# Arduino_Uno.net
KiCad netlist of a schematic drawn in EAGLE
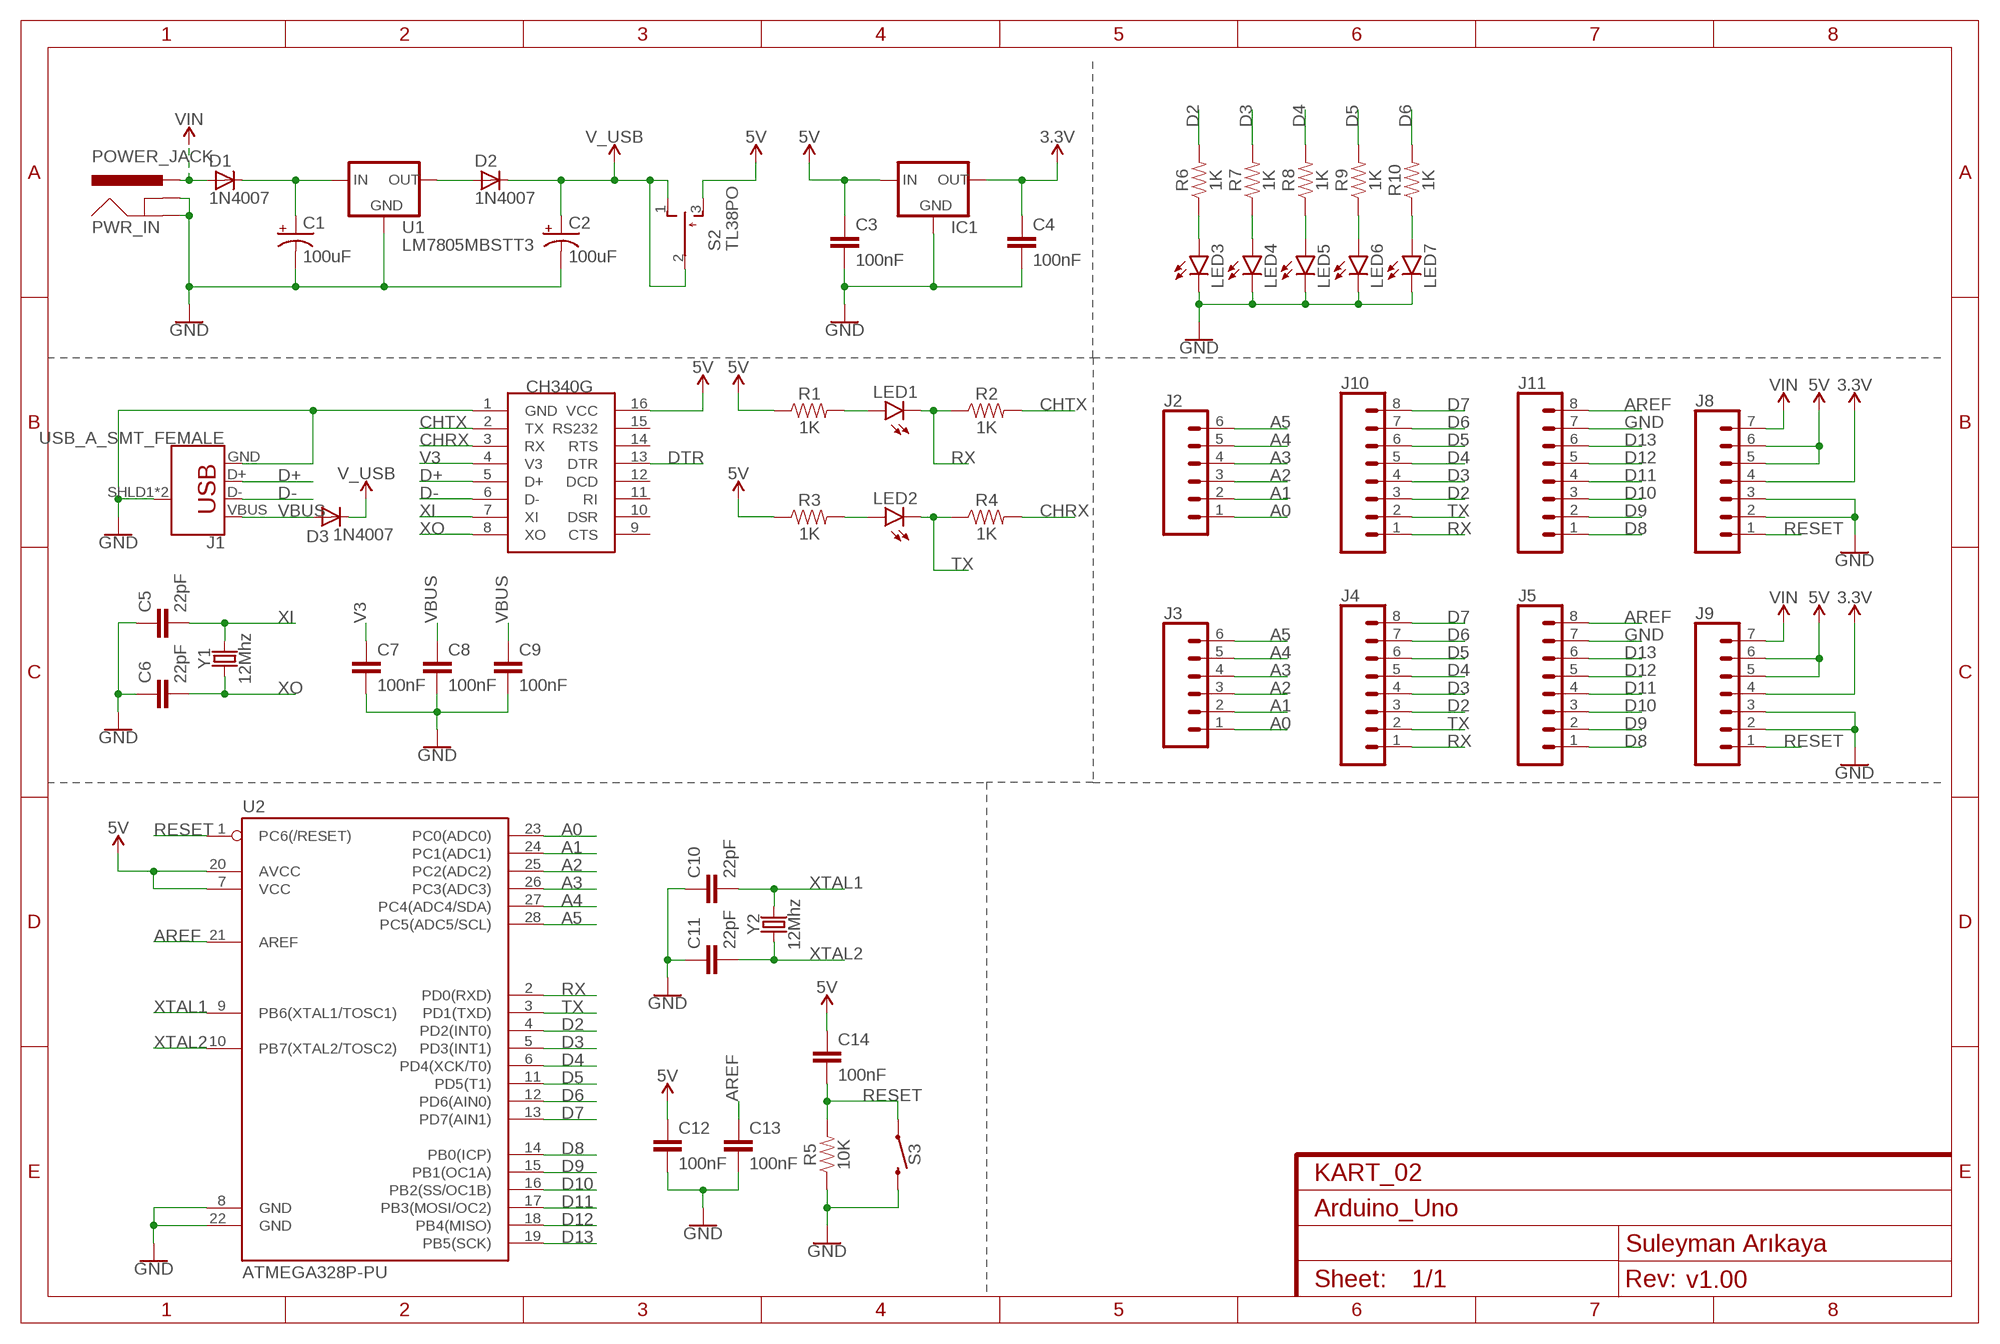
[diagram p0: schematic, sheet 1]

(export (version "E")
  (design (tool "Eeschema 10.0.6"))
  (components
    (comp (ref "C1")
      (value "100uF")
      (footprint "eagle-import:PANASONIC_D")
      (libsource (lib "eagle-import") (part "100UF-POLAR-25V-20%(ELEC)"))
    )
    (comp (ref "C2")
      (value "100uF")
      (footprint "eagle-import:PANASONIC_D")
      (libsource (lib "eagle-import") (part "100UF-POLAR-25V-20%(ELEC)"))
    )
    (comp (ref "C3")
      (value "100nF")
      (footprint "eagle-import:0805")
      (libsource (lib "eagle-import") (part "1.0UF-0805-25V-10%"))
    )
    (comp (ref "C4")
      (value "100nF")
      (footprint "eagle-import:0805")
      (libsource (lib "eagle-import") (part "1.0UF-0805-25V-10%"))
    )
    (comp (ref "C5")
      (value "22pF")
      (footprint "eagle-import:0805")
      (libsource (lib "eagle-import") (part "1.0UF-0805-25V-10%"))
    )
    (comp (ref "C6")
      (value "22pF")
      (footprint "eagle-import:0805")
      (libsource (lib "eagle-import") (part "1.0UF-0805-25V-10%"))
    )
    (comp (ref "C7")
      (value "100nF")
      (footprint "eagle-import:0805")
      (libsource (lib "eagle-import") (part "1.0UF-0805-25V-10%"))
    )
    (comp (ref "C8")
      (value "100nF")
      (footprint "eagle-import:0805")
      (libsource (lib "eagle-import") (part "1.0UF-0805-25V-10%"))
    )
    (comp (ref "C9")
      (value "100nF")
      (footprint "eagle-import:0805")
      (libsource (lib "eagle-import") (part "1.0UF-0805-25V-10%"))
    )
    (comp (ref "C10")
      (value "22pF")
      (footprint "eagle-import:0805")
      (libsource (lib "eagle-import") (part "1.0UF-0805-25V-10%"))
    )
    (comp (ref "C11")
      (value "22pF")
      (footprint "eagle-import:0805")
      (libsource (lib "eagle-import") (part "1.0UF-0805-25V-10%"))
    )
    (comp (ref "C12")
      (value "100nF")
      (footprint "eagle-import:0805")
      (libsource (lib "eagle-import") (part "1.0UF-0805-25V-10%"))
    )
    (comp (ref "C13")
      (value "100nF")
      (footprint "eagle-import:0805")
      (libsource (lib "eagle-import") (part "1.0UF-0805-25V-10%"))
    )
    (comp (ref "C14")
      (value "100nF")
      (footprint "eagle-import:0805")
      (libsource (lib "eagle-import") (part "1.0UF-0805-25V-10%"))
    )
    (comp (ref "D1")
      (value "1N4007")
      (footprint "eagle-import:SMA")
      (libsource (lib "eagle-import") (part "1N4007"))
    )
    (comp (ref "D2")
      (value "1N4007")
      (footprint "eagle-import:SMA")
      (libsource (lib "eagle-import") (part "1N4007"))
    )
    (comp (ref "D3")
      (value "1N4007")
      (footprint "eagle-import:SMA")
      (libsource (lib "eagle-import") (part "1N4007"))
    )
    (comp (ref "IC1")
      (value "LM1117")
      (footprint "eagle-import:SOT223")
      (libsource (lib "eagle-import") (part "LM1117"))
    )
    (comp (ref "J1")
      (value "USB_A_SMT_FEMALE")
      (footprint "eagle-import:USB-A-S-SILK-FEMALE")
      (libsource (lib "eagle-import") (part "USB_A_SMT_FEMALE"))
    )
    (comp (ref "J2")
      (value "CONN_06NO_SILK_FEMALE_PTH")
      (footprint "eagle-import:1X06_NO_SILK")
      (libsource (lib "eagle-import") (part "CONN_06NO_SILK_FEMALE_PTH"))
    )
    (comp (ref "J3")
      (value "CONN_06NO_SILK_FEMALE_PTH")
      (footprint "eagle-import:1X06_NO_SILK")
      (libsource (lib "eagle-import") (part "CONN_06NO_SILK_FEMALE_PTH"))
    )
    (comp (ref "J4")
      (value "CONN_08\"")
      (footprint "eagle-import:1X08")
      (libsource (lib "eagle-import") (part "CONN_08{dblquote}"))
    )
    (comp (ref "J5")
      (value "CONN_08\"")
      (footprint "eagle-import:1X08")
      (libsource (lib "eagle-import") (part "CONN_08{dblquote}"))
    )
    (comp (ref "J8")
      (value "CONN_07")
      (footprint "eagle-import:1X07")
      (libsource (lib "eagle-import") (part "CONN_07"))
    )
    (comp (ref "J9")
      (value "CONN_07")
      (footprint "eagle-import:1X07")
      (libsource (lib "eagle-import") (part "CONN_07"))
    )
    (comp (ref "J10")
      (value "CONN_08\"")
      (footprint "eagle-import:1X08")
      (libsource (lib "eagle-import") (part "CONN_08{dblquote}"))
    )
    (comp (ref "J11")
      (value "CONN_08\"")
      (footprint "eagle-import:1X08")
      (libsource (lib "eagle-import") (part "CONN_08{dblquote}"))
    )
    (comp (ref "LED1")
      (value "LEDSML0805")
      (footprint "eagle-import:SML0805")
      (libsource (lib "eagle-import") (part "LEDSML0805"))
    )
    (comp (ref "LED2")
      (value "LEDSML0805")
      (footprint "eagle-import:SML0805")
      (libsource (lib "eagle-import") (part "LEDSML0805"))
    )
    (comp (ref "LED3")
      (value "LEDSML0805")
      (footprint "eagle-import:SML0805")
      (libsource (lib "eagle-import") (part "LEDSML0805"))
    )
    (comp (ref "LED4")
      (value "LEDSML0805")
      (footprint "eagle-import:SML0805")
      (libsource (lib "eagle-import") (part "LEDSML0805"))
    )
    (comp (ref "LED5")
      (value "LEDSML0805")
      (footprint "eagle-import:SML0805")
      (libsource (lib "eagle-import") (part "LEDSML0805"))
    )
    (comp (ref "LED6")
      (value "LEDSML0805")
      (footprint "eagle-import:SML0805")
      (libsource (lib "eagle-import") (part "LEDSML0805"))
    )
    (comp (ref "LED7")
      (value "LEDSML0805")
      (footprint "eagle-import:SML0805")
      (libsource (lib "eagle-import") (part "LEDSML0805"))
    )
    (comp (ref "PWR_IN")
      (value "POWER_JACK")
      (footprint "eagle-import:POWER_JACK_PTH")
      (libsource (lib "eagle-import") (part "POWER_JACK"))
    )
    (comp (ref "R1")
      (value "1K")
      (footprint "eagle-import:0805")
      (libsource (lib "eagle-import") (part "RESISTOR0805"))
    )
    (comp (ref "R2")
      (value "1K")
      (footprint "eagle-import:0805")
      (libsource (lib "eagle-import") (part "RESISTOR0805"))
    )
    (comp (ref "R3")
      (value "1K")
      (footprint "eagle-import:0805")
      (libsource (lib "eagle-import") (part "RESISTOR0805"))
    )
    (comp (ref "R4")
      (value "1K")
      (footprint "eagle-import:0805")
      (libsource (lib "eagle-import") (part "RESISTOR0805"))
    )
    (comp (ref "R5")
      (value "10K")
      (footprint "eagle-import:0805")
      (libsource (lib "eagle-import") (part "RESISTOR0805"))
    )
    (comp (ref "R6")
      (value "1K")
      (footprint "eagle-import:0805")
      (libsource (lib "eagle-import") (part "RESISTOR0805"))
    )
    (comp (ref "R7")
      (value "1K")
      (footprint "eagle-import:0805")
      (libsource (lib "eagle-import") (part "RESISTOR0805"))
    )
    (comp (ref "R8")
      (value "1K")
      (footprint "eagle-import:0805")
      (libsource (lib "eagle-import") (part "RESISTOR0805"))
    )
    (comp (ref "R9")
      (value "1K")
      (footprint "eagle-import:0805")
      (libsource (lib "eagle-import") (part "RESISTOR0805"))
    )
    (comp (ref "R10")
      (value "1K")
      (footprint "eagle-import:0805")
      (libsource (lib "eagle-import") (part "RESISTOR0805"))
    )
    (comp (ref "S2")
      (value "TL38PO")
      (footprint "eagle-import:TL3XPO")
      (libsource (lib "eagle-import") (part "TL38PO"))
    )
    (comp (ref "S3")
      (value "MOMENTARY-SWITCH-SPST-PTH-6.0MM")
      (footprint "eagle-import:TACTILE_SWITCH_PTH_6.0MM")
      (libsource (lib "eagle-import") (part "MOMENTARY-SWITCH-SPST-PTH-6.0MM"))
    )
    (comp (ref "U$1")
      (value "CH340G")
      (footprint "eagle-import:SOIC16")
      (libsource (lib "eagle-import") (part "CH340G"))
    )
    (comp (ref "U1")
      (value "LM7805MBSTT3")
      (footprint "eagle-import:D2PAK")
      (libsource (lib "eagle-import") (part "L78XXD2TT"))
    )
    (comp (ref "U2")
      (value "ATMEGA328P-PU")
      (footprint "eagle-import:DIP28")
      (libsource (lib "eagle-import") (part "ATMEGA328P_PDIP"))
    )
    (comp (ref "Y1")
      (value "12Mhz")
      (footprint "eagle-import:HC49UP")
      (libsource (lib "eagle-import") (part "CRYSTALSMD-HC49UP"))
    )
    (comp (ref "Y2")
      (value "12Mhz")
      (footprint "eagle-import:HC49UP")
      (libsource (lib "eagle-import") (part "CRYSTALSMD-HC49UP"))
    )
  )
  (nets
    (net (code "1") (name "/A0") (class "Default")
      (node (ref "J2") (pin "1") (pinfunction "1_1") (pintype "passive"))
      (node (ref "J3") (pin "1") (pinfunction "1_1") (pintype "passive"))
      (node (ref "U2") (pin "23") (pinfunction "PC0(ADC0)_23") (pintype "bidirectional"))
    )
    (net (code "2") (name "/A1") (class "Default")
      (node (ref "J2") (pin "2") (pinfunction "2_2") (pintype "passive"))
      (node (ref "J3") (pin "2") (pinfunction "2_2") (pintype "passive"))
      (node (ref "U2") (pin "24") (pinfunction "PC1(ADC1)_24") (pintype "bidirectional"))
    )
    (net (code "3") (name "/A2") (class "Default")
      (node (ref "J2") (pin "3") (pinfunction "3_3") (pintype "passive"))
      (node (ref "J3") (pin "3") (pinfunction "3_3") (pintype "passive"))
      (node (ref "U2") (pin "25") (pinfunction "PC2(ADC2)_25") (pintype "bidirectional"))
    )
    (net (code "4") (name "/A3") (class "Default")
      (node (ref "J2") (pin "4") (pinfunction "4_4") (pintype "passive"))
      (node (ref "J3") (pin "4") (pinfunction "4_4") (pintype "passive"))
      (node (ref "U2") (pin "26") (pinfunction "PC3(ADC3)_26") (pintype "bidirectional"))
    )
    (net (code "5") (name "/A4") (class "Default")
      (node (ref "J2") (pin "5") (pinfunction "5_5") (pintype "passive"))
      (node (ref "J3") (pin "5") (pinfunction "5_5") (pintype "passive"))
      (node (ref "U2") (pin "27") (pinfunction "PC4(ADC4/SDA)_27") (pintype "bidirectional"))
    )
    (net (code "6") (name "/A5") (class "Default")
      (node (ref "J2") (pin "6") (pinfunction "6_6") (pintype "passive"))
      (node (ref "J3") (pin "6") (pinfunction "6_6") (pintype "passive"))
      (node (ref "U2") (pin "28") (pinfunction "PC5(ADC5/SCL)_28") (pintype "bidirectional"))
    )
    (net (code "7") (name "/AREF") (class "Default")
      (node (ref "C13") (pin "1") (pinfunction "1_1") (pintype "passive"))
      (node (ref "J11") (pin "8") (pinfunction "8_8") (pintype "passive"))
      (node (ref "J5") (pin "8") (pinfunction "8_8") (pintype "passive"))
      (node (ref "U2") (pin "21") (pinfunction "AREF_21") (pintype "bidirectional"))
    )
    (net (code "8") (name "/CHRX") (class "Default")
      (node (ref "R4") (pin "2") (pinfunction "2_2") (pintype "passive"))
      (node (ref "U$1") (pin "3") (pinfunction "RX_3") (pintype "bidirectional"))
    )
    (net (code "9") (name "/CHTX") (class "Default")
      (node (ref "R2") (pin "2") (pinfunction "2_2") (pintype "passive"))
      (node (ref "U$1") (pin "2") (pinfunction "TX_2") (pintype "bidirectional"))
    )
    (net (code "10") (name "/D+") (class "Default")
      (node (ref "J1") (pin "D+") (pinfunction "D+_D+") (pintype "bidirectional"))
      (node (ref "U$1") (pin "5") (pinfunction "D+_5") (pintype "bidirectional"))
    )
    (net (code "11") (name "/D-") (class "Default")
      (node (ref "J1") (pin "D-") (pinfunction "D-_D-") (pintype "bidirectional"))
      (node (ref "U$1") (pin "6") (pinfunction "D-_6") (pintype "bidirectional"))
    )
    (net (code "12") (name "/D2") (class "Default")
      (node (ref "J10") (pin "3") (pinfunction "3_3") (pintype "passive"))
      (node (ref "J4") (pin "3") (pinfunction "3_3") (pintype "passive"))
      (node (ref "R6") (pin "2") (pinfunction "2_2") (pintype "passive"))
      (node (ref "U2") (pin "4") (pinfunction "PD2(INT0)_4") (pintype "bidirectional"))
    )
    (net (code "13") (name "/D3") (class "Default")
      (node (ref "J10") (pin "4") (pinfunction "4_4") (pintype "passive"))
      (node (ref "J4") (pin "4") (pinfunction "4_4") (pintype "passive"))
      (node (ref "R7") (pin "2") (pinfunction "2_2") (pintype "passive"))
      (node (ref "U2") (pin "5") (pinfunction "PD3(INT1)_5") (pintype "bidirectional"))
    )
    (net (code "14") (name "/D4") (class "Default")
      (node (ref "J10") (pin "5") (pinfunction "5_5") (pintype "passive"))
      (node (ref "J4") (pin "5") (pinfunction "5_5") (pintype "passive"))
      (node (ref "R8") (pin "2") (pinfunction "2_2") (pintype "passive"))
      (node (ref "U2") (pin "6") (pinfunction "PD4(XCK/T0)_6") (pintype "bidirectional"))
    )
    (net (code "15") (name "/D5") (class "Default")
      (node (ref "J10") (pin "6") (pinfunction "6_6") (pintype "passive"))
      (node (ref "J4") (pin "6") (pinfunction "6_6") (pintype "passive"))
      (node (ref "R9") (pin "2") (pinfunction "2_2") (pintype "passive"))
      (node (ref "U2") (pin "11") (pinfunction "PD5(T1)_11") (pintype "bidirectional"))
    )
    (net (code "16") (name "/D6") (class "Default")
      (node (ref "J10") (pin "7") (pinfunction "7_7") (pintype "passive"))
      (node (ref "J4") (pin "7") (pinfunction "7_7") (pintype "passive"))
      (node (ref "R10") (pin "2") (pinfunction "2_2") (pintype "passive"))
      (node (ref "U2") (pin "12") (pinfunction "PD6(AIN0)_12") (pintype "bidirectional"))
    )
    (net (code "17") (name "/D7") (class "Default")
      (node (ref "J10") (pin "8") (pinfunction "8_8") (pintype "passive"))
      (node (ref "J4") (pin "8") (pinfunction "8_8") (pintype "passive"))
      (node (ref "U2") (pin "13") (pinfunction "PD7(AIN1)_13") (pintype "bidirectional"))
    )
    (net (code "18") (name "/D8") (class "Default")
      (node (ref "J11") (pin "1") (pinfunction "1_1") (pintype "passive"))
      (node (ref "J5") (pin "1") (pinfunction "1_1") (pintype "passive"))
      (node (ref "U2") (pin "14") (pinfunction "PB0(ICP)_14") (pintype "bidirectional"))
    )
    (net (code "19") (name "/D9") (class "Default")
      (node (ref "J11") (pin "2") (pinfunction "2_2") (pintype "passive"))
      (node (ref "J5") (pin "2") (pinfunction "2_2") (pintype "passive"))
      (node (ref "U2") (pin "15") (pinfunction "PB1(OC1A)_15") (pintype "bidirectional"))
    )
    (net (code "20") (name "/D10") (class "Default")
      (node (ref "J11") (pin "3") (pinfunction "3_3") (pintype "passive"))
      (node (ref "J5") (pin "3") (pinfunction "3_3") (pintype "passive"))
      (node (ref "U2") (pin "16") (pinfunction "PB2(SS/OC1B)_16") (pintype "bidirectional"))
    )
    (net (code "21") (name "/D11") (class "Default")
      (node (ref "J11") (pin "4") (pinfunction "4_4") (pintype "passive"))
      (node (ref "J5") (pin "4") (pinfunction "4_4") (pintype "passive"))
      (node (ref "U2") (pin "17") (pinfunction "PB3(MOSI/OC2)_17") (pintype "bidirectional"))
    )
    (net (code "22") (name "/D12") (class "Default")
      (node (ref "J11") (pin "5") (pinfunction "5_5") (pintype "passive"))
      (node (ref "J5") (pin "5") (pinfunction "5_5") (pintype "passive"))
      (node (ref "U2") (pin "18") (pinfunction "PB4(MISO)_18") (pintype "bidirectional"))
    )
    (net (code "23") (name "/D13") (class "Default")
      (node (ref "J11") (pin "6") (pinfunction "6_6") (pintype "passive"))
      (node (ref "J5") (pin "6") (pinfunction "6_6") (pintype "passive"))
      (node (ref "U2") (pin "19") (pinfunction "PB5(SCK)_19") (pintype "bidirectional"))
    )
    (net (code "24") (name "/DTR") (class "Default")
      (node (ref "U$1") (pin "13") (pinfunction "DTR_13") (pintype "bidirectional"))
    )
    (net (code "25") (name "/RESET") (class "Default")
      (node (ref "C14") (pin "2") (pinfunction "2_2") (pintype "passive"))
      (node (ref "J8") (pin "1") (pinfunction "1_1") (pintype "passive"))
      (node (ref "J9") (pin "1") (pinfunction "1_1") (pintype "passive"))
      (node (ref "R5") (pin "2") (pinfunction "2_2") (pintype "passive"))
      (node (ref "S3") (pin "1") (pinfunction "1_1") (pintype "passive"))
      (node (ref "U2") (pin "1") (pinfunction "PC6(/RESET)_1") (pintype "bidirectional"))
    )
    (net (code "26") (name "/RX") (class "Default")
      (node (ref "J10") (pin "1") (pinfunction "1_1") (pintype "passive"))
      (node (ref "J4") (pin "1") (pinfunction "1_1") (pintype "passive"))
      (node (ref "LED1") (pin "C") (pinfunction "C_C") (pintype "passive"))
      (node (ref "R2") (pin "1") (pinfunction "1_1") (pintype "passive"))
      (node (ref "U2") (pin "2") (pinfunction "PD0(RXD)_2") (pintype "bidirectional"))
    )
    (net (code "27") (name "/TX") (class "Default")
      (node (ref "J10") (pin "2") (pinfunction "2_2") (pintype "passive"))
      (node (ref "J4") (pin "2") (pinfunction "2_2") (pintype "passive"))
      (node (ref "LED2") (pin "C") (pinfunction "C_C") (pintype "passive"))
      (node (ref "R4") (pin "1") (pinfunction "1_1") (pintype "passive"))
      (node (ref "U2") (pin "3") (pinfunction "PD1(TXD)_3") (pintype "bidirectional"))
    )
    (net (code "28") (name "/V3") (class "Default")
      (node (ref "C7") (pin "1") (pinfunction "1_1") (pintype "passive"))
      (node (ref "U$1") (pin "4") (pinfunction "V3_4") (pintype "bidirectional"))
    )
    (net (code "29") (name "/VBUS") (class "Default")
      (node (ref "C8") (pin "1") (pinfunction "1_1") (pintype "passive"))
      (node (ref "C9") (pin "1") (pinfunction "1_1") (pintype "passive"))
      (node (ref "D3") (pin "A") (pinfunction "A_A") (pintype "passive"))
      (node (ref "J1") (pin "VBUS") (pinfunction "VBUS_VBUS") (pintype "power_in"))
    )
    (net (code "30") (name "/XI") (class "Default")
      (node (ref "C5") (pin "2") (pinfunction "2_2") (pintype "passive"))
      (node (ref "U$1") (pin "7") (pinfunction "XI_7") (pintype "bidirectional"))
      (node (ref "Y1") (pin "2") (pinfunction "2_2") (pintype "passive"))
    )
    (net (code "31") (name "/XO") (class "Default")
      (node (ref "C6") (pin "2") (pinfunction "2_2") (pintype "passive"))
      (node (ref "U$1") (pin "8") (pinfunction "XO_8") (pintype "bidirectional"))
      (node (ref "Y1") (pin "1") (pinfunction "1_1") (pintype "passive"))
    )
    (net (code "32") (name "/XTAL1") (class "Default")
      (node (ref "C10") (pin "2") (pinfunction "2_2") (pintype "passive"))
      (node (ref "U2") (pin "9") (pinfunction "PB6(XTAL1/TOSC1)_9") (pintype "bidirectional"))
      (node (ref "Y2") (pin "2") (pinfunction "2_2") (pintype "passive"))
    )
    (net (code "33") (name "/XTAL2") (class "Default")
      (node (ref "C11") (pin "2") (pinfunction "2_2") (pintype "passive"))
      (node (ref "U2") (pin "10") (pinfunction "PB7(XTAL2/TOSC2)_10") (pintype "bidirectional"))
      (node (ref "Y2") (pin "1") (pinfunction "1_1") (pintype "passive"))
    )
    (net (code "34") (name "3.3V") (class "Default")
      (node (ref "C4") (pin "1") (pinfunction "1_1") (pintype "passive"))
      (node (ref "IC1") (pin "2") (pinfunction "OUT_2") (pintype "passive"))
      (node (ref "J8") (pin "4") (pinfunction "4_4") (pintype "passive"))
      (node (ref "J9") (pin "4") (pinfunction "4_4") (pintype "passive"))
    )
    (net (code "35") (name "5V") (class "Default")
      (node (ref "C12") (pin "1") (pinfunction "1_1") (pintype "passive"))
      (node (ref "C14") (pin "1") (pinfunction "1_1") (pintype "passive"))
      (node (ref "C3") (pin "1") (pinfunction "1_1") (pintype "passive"))
      (node (ref "IC1") (pin "3") (pinfunction "IN_3") (pintype "input"))
      (node (ref "J8") (pin "5") (pinfunction "5_5") (pintype "passive"))
      (node (ref "J8") (pin "6") (pinfunction "6_6") (pintype "passive"))
      (node (ref "J9") (pin "5") (pinfunction "5_5") (pintype "passive"))
      (node (ref "J9") (pin "6") (pinfunction "6_6") (pintype "passive"))
      (node (ref "R1") (pin "1") (pinfunction "1_1") (pintype "passive"))
      (node (ref "R3") (pin "1") (pinfunction "1_1") (pintype "passive"))
      (node (ref "S2") (pin "3") (pinfunction "S_3") (pintype "passive"))
      (node (ref "U$1") (pin "16") (pinfunction "VCC_16") (pintype "bidirectional"))
      (node (ref "U2") (pin "20") (pinfunction "AVCC_20") (pintype "bidirectional"))
      (node (ref "U2") (pin "7") (pinfunction "VCC_7") (pintype "bidirectional"))
    )
    (net (code "36") (name "GND") (class "Default")
      (node (ref "C1") (pin "-") (pinfunction "-_-") (pintype "passive"))
      (node (ref "C10") (pin "1") (pinfunction "1_1") (pintype "passive"))
      (node (ref "C11") (pin "1") (pinfunction "1_1") (pintype "passive"))
      (node (ref "C12") (pin "2") (pinfunction "2_2") (pintype "passive"))
      (node (ref "C13") (pin "2") (pinfunction "2_2") (pintype "passive"))
      (node (ref "C2") (pin "-") (pinfunction "-_-") (pintype "passive"))
      (node (ref "C3") (pin "2") (pinfunction "2_2") (pintype "passive"))
      (node (ref "C4") (pin "2") (pinfunction "2_2") (pintype "passive"))
      (node (ref "C5") (pin "1") (pinfunction "1_1") (pintype "passive"))
      (node (ref "C6") (pin "1") (pinfunction "1_1") (pintype "passive"))
      (node (ref "C7") (pin "2") (pinfunction "2_2") (pintype "passive"))
      (node (ref "C8") (pin "2") (pinfunction "2_2") (pintype "passive"))
      (node (ref "C9") (pin "2") (pinfunction "2_2") (pintype "passive"))
      (node (ref "IC1") (pin "1") (pinfunction "GND_1") (pintype "input"))
      (node (ref "J1") (pin "GND") (pinfunction "GND_GND") (pintype "power_in"))
      (node (ref "J1") (pin "SHLD1") (pinfunction "SHIELD_SHLD1") (pintype "bidirectional"))
      (node (ref "J1") (pin "SHLD2") (pinfunction "SHIELD_SHLD2") (pintype "bidirectional"))
      (node (ref "J11") (pin "7") (pinfunction "7_7") (pintype "passive"))
      (node (ref "J5") (pin "7") (pinfunction "7_7") (pintype "passive"))
      (node (ref "J8") (pin "2") (pinfunction "2_2") (pintype "passive"))
      (node (ref "J8") (pin "3") (pinfunction "3_3") (pintype "passive"))
      (node (ref "J9") (pin "2") (pinfunction "2_2") (pintype "passive"))
      (node (ref "J9") (pin "3") (pinfunction "3_3") (pintype "passive"))
      (node (ref "LED3") (pin "C") (pinfunction "C_C") (pintype "passive"))
      (node (ref "LED4") (pin "C") (pinfunction "C_C") (pintype "passive"))
      (node (ref "LED5") (pin "C") (pinfunction "C_C") (pintype "passive"))
      (node (ref "LED6") (pin "C") (pinfunction "C_C") (pintype "passive"))
      (node (ref "LED7") (pin "C") (pinfunction "C_C") (pintype "passive"))
      (node (ref "PWR_IN") (pin "GND") (pinfunction "GND_GND") (pintype "bidirectional"))
      (node (ref "PWR_IN") (pin "GNDBREAK") (pinfunction "GNDBREAK_GNDBREAK") (pintype "bidirectional"))
      (node (ref "R5") (pin "1") (pinfunction "1_1") (pintype "passive"))
      (node (ref "S3") (pin "3") (pinfunction "2_3") (pintype "passive"))
      (node (ref "U$1") (pin "1") (pinfunction "GND_1") (pintype "bidirectional"))
      (node (ref "U1") (pin "2") (pinfunction "GND_2") (pintype "input"))
      (node (ref "U2") (pin "22") (pinfunction "GND_22") (pintype "bidirectional"))
      (node (ref "U2") (pin "8") (pinfunction "GND_8") (pintype "bidirectional"))
    )
    (net (code "37") (name "Net-(D1-C)") (class "Default")
      (node (ref "C1") (pin "+") (pinfunction "+_+") (pintype "passive"))
      (node (ref "D1") (pin "K") (pinfunction "C_K") (pintype "passive"))
      (node (ref "U1") (pin "1") (pinfunction "IN_1") (pintype "input"))
    )
    (net (code "38") (name "Net-(LED1-PadA)") (class "Default")
      (node (ref "LED1") (pin "A") (pinfunction "A_A") (pintype "passive"))
      (node (ref "R1") (pin "2") (pinfunction "2_2") (pintype "passive"))
    )
    (net (code "39") (name "Net-(LED2-PadA)") (class "Default")
      (node (ref "LED2") (pin "A") (pinfunction "A_A") (pintype "passive"))
      (node (ref "R3") (pin "2") (pinfunction "2_2") (pintype "passive"))
    )
    (net (code "40") (name "Net-(LED3-PadA)") (class "Default")
      (node (ref "LED3") (pin "A") (pinfunction "A_A") (pintype "passive"))
      (node (ref "R6") (pin "1") (pinfunction "1_1") (pintype "passive"))
    )
    (net (code "41") (name "Net-(LED4-PadA)") (class "Default")
      (node (ref "LED4") (pin "A") (pinfunction "A_A") (pintype "passive"))
      (node (ref "R7") (pin "1") (pinfunction "1_1") (pintype "passive"))
    )
    (net (code "42") (name "Net-(LED5-PadA)") (class "Default")
      (node (ref "LED5") (pin "A") (pinfunction "A_A") (pintype "passive"))
      (node (ref "R8") (pin "1") (pinfunction "1_1") (pintype "passive"))
    )
    (net (code "43") (name "Net-(LED6-PadA)") (class "Default")
      (node (ref "LED6") (pin "A") (pinfunction "A_A") (pintype "passive"))
      (node (ref "R9") (pin "1") (pinfunction "1_1") (pintype "passive"))
    )
    (net (code "44") (name "Net-(LED7-PadA)") (class "Default")
      (node (ref "LED7") (pin "A") (pinfunction "A_A") (pintype "passive"))
      (node (ref "R10") (pin "1") (pinfunction "1_1") (pintype "passive"))
    )
    (net (code "45") (name "Net-(U1-OUT)") (class "Default")
      (node (ref "D2") (pin "A") (pinfunction "A_A") (pintype "passive"))
      (node (ref "U1") (pin "3") (pinfunction "OUT_3") (pintype "passive"))
    )
    (net (code "46") (name "VIN") (class "Default")
      (node (ref "D1") (pin "A") (pinfunction "A_A") (pintype "passive"))
      (node (ref "J8") (pin "7") (pinfunction "7_7") (pintype "passive"))
      (node (ref "J9") (pin "7") (pinfunction "7_7") (pintype "passive"))
      (node (ref "PWR_IN") (pin "PWR") (pinfunction "PWR_PWR") (pintype "bidirectional"))
    )
    (net (code "47") (name "V_USB") (class "Default")
      (node (ref "C2") (pin "+") (pinfunction "+_+") (pintype "passive"))
      (node (ref "D2") (pin "K") (pinfunction "C_K") (pintype "passive"))
      (node (ref "D3") (pin "K") (pinfunction "C_K") (pintype "passive"))
      (node (ref "S2") (pin "1") (pinfunction "O_1") (pintype "passive"))
      (node (ref "S2") (pin "2") (pinfunction "P_2") (pintype "passive"))
    )
    (net (code "48") (name "unconnected-(U$1-CTS-Pad9)") (class "Default")
      (node (ref "U$1") (pin "9") (pinfunction "CTS_9") (pintype "bidirectional"))
    )
    (net (code "49") (name "unconnected-(U$1-DCD-Pad12)") (class "Default")
      (node (ref "U$1") (pin "12") (pinfunction "DCD_12") (pintype "bidirectional"))
    )
    (net (code "50") (name "unconnected-(U$1-DSR-Pad10)") (class "Default")
      (node (ref "U$1") (pin "10") (pinfunction "DSR_10") (pintype "bidirectional"))
    )
    (net (code "51") (name "unconnected-(U$1-RI-Pad11)") (class "Default")
      (node (ref "U$1") (pin "11") (pinfunction "RI_11") (pintype "bidirectional"))
    )
    (net (code "52") (name "unconnected-(U$1-RS232-Pad15)") (class "Default")
      (node (ref "U$1") (pin "15") (pinfunction "RS232_15") (pintype "bidirectional"))
    )
    (net (code "53") (name "unconnected-(U$1-RTS-Pad14)") (class "Default")
      (node (ref "U$1") (pin "14") (pinfunction "RTS_14") (pintype "bidirectional"))
    )
  )
)
